# meter_mode.net
KiCad netlist of a schematic drawn in EAGLE
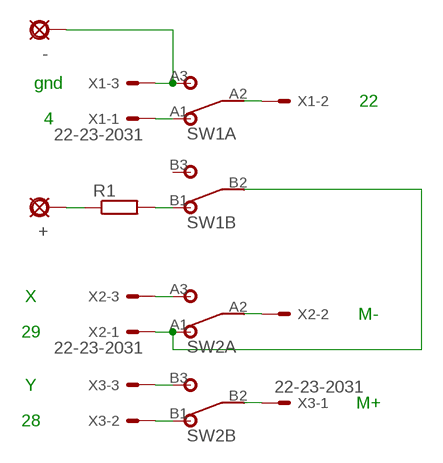
[diagram p0: schematic, sheet 1]

(export (version "E")
  (design (tool "Eeschema 10.0.6"))
  (components
    (comp (ref "+")
      (value "PADO")
      (footprint "eagle-import:ROUND")
      (libsource (lib "eagle-import") (part "PADO"))
    )
    (comp (ref "-")
      (value "PAD")
      (footprint "eagle-import:SQUARE")
      (libsource (lib "eagle-import") (part "PAD"))
    )
    (comp (ref "R1")
      (value "R-EU_0204/2V")
      (footprint "eagle-import:0204V")
      (libsource (lib "eagle-import") (part "R-EU_0204/2V"))
    )
    (comp (ref "SW1")
      (value "DPDT")
      (footprint "eagle-import:DPDT")
      (libsource (lib "eagle-import") (part "DPDT"))
    )
    (comp (ref "SW2")
      (value "DPDT")
      (footprint "eagle-import:DPDT")
      (libsource (lib "eagle-import") (part "DPDT"))
    )
    (comp (ref "X1")
      (value "22-23-2031")
      (footprint "eagle-import:22-23-2031")
      (fields (field (name "MF") "MOLEX"))
      (libsource (lib "eagle-import") (part "22-23-2031"))
    )
    (comp (ref "X2")
      (value "22-23-2031")
      (footprint "eagle-import:22-23-2031")
      (fields (field (name "MF") "MOLEX"))
      (libsource (lib "eagle-import") (part "22-23-2031"))
    )
    (comp (ref "X3")
      (value "22-23-2031")
      (footprint "eagle-import:22-23-2031")
      (fields (field (name "MF") "MOLEX"))
      (libsource (lib "eagle-import") (part "22-23-2031"))
    )
  )
  (nets
    (net (code "1") (name "Net-(+-PAD)") (class "Default")
      (node (ref "+") (pin "1") (pinfunction "PAD_1") (pintype "passive"))
      (node (ref "R1") (pin "1") (pinfunction "1_1") (pintype "passive"))
    )
    (net (code "2") (name "Net-(--PAD)") (class "Default")
      (node (ref "-") (pin "1") (pinfunction "PAD_1") (pintype "passive"))
      (node (ref "SW1") (pin "A3") (pinfunction "3_A3") (pintype "passive"))
      (node (ref "X1") (pin "3") (pinfunction "S_3") (pintype "passive"))
    )
    (net (code "3") (name "Net-(SW1A-1)") (class "Default")
      (node (ref "SW1") (pin "A1") (pinfunction "1_A1") (pintype "passive"))
      (node (ref "X1") (pin "1") (pinfunction "S_1") (pintype "passive"))
    )
    (net (code "4") (name "Net-(SW1A-2)") (class "Default")
      (node (ref "SW1") (pin "A2") (pinfunction "2_A2") (pintype "passive"))
      (node (ref "X1") (pin "2") (pinfunction "S_2") (pintype "passive"))
    )
    (net (code "5") (name "Net-(SW1B-1)") (class "Default")
      (node (ref "R1") (pin "2") (pinfunction "2_2") (pintype "passive"))
      (node (ref "SW1") (pin "B1") (pinfunction "1_B1") (pintype "passive"))
    )
    (net (code "6") (name "Net-(SW1B-2)") (class "Default")
      (node (ref "SW1") (pin "B2") (pinfunction "2_B2") (pintype "passive"))
      (node (ref "SW2") (pin "A1") (pinfunction "1_A1") (pintype "passive"))
      (node (ref "X2") (pin "1") (pinfunction "S_1") (pintype "passive"))
    )
    (net (code "7") (name "Net-(SW2A-2)") (class "Default")
      (node (ref "SW2") (pin "A2") (pinfunction "2_A2") (pintype "passive"))
      (node (ref "X2") (pin "2") (pinfunction "S_2") (pintype "passive"))
    )
    (net (code "8") (name "Net-(SW2A-3)") (class "Default")
      (node (ref "SW2") (pin "A3") (pinfunction "3_A3") (pintype "passive"))
      (node (ref "X2") (pin "3") (pinfunction "S_3") (pintype "passive"))
    )
    (net (code "9") (name "Net-(SW2B-1)") (class "Default")
      (node (ref "SW2") (pin "B1") (pinfunction "1_B1") (pintype "passive"))
      (node (ref "X3") (pin "2") (pinfunction "S_2") (pintype "passive"))
    )
    (net (code "10") (name "Net-(SW2B-2)") (class "Default")
      (node (ref "SW2") (pin "B2") (pinfunction "2_B2") (pintype "passive"))
      (node (ref "X3") (pin "1") (pinfunction "S_1") (pintype "passive"))
    )
    (net (code "11") (name "Net-(SW2B-3)") (class "Default")
      (node (ref "SW2") (pin "B3") (pinfunction "3_B3") (pintype "passive"))
      (node (ref "X3") (pin "3") (pinfunction "S_3") (pintype "passive"))
    )
    (net (code "12") (name "unconnected-(SW1B-3-PadB3)") (class "Default")
      (node (ref "SW1") (pin "B3") (pinfunction "3_B3") (pintype "passive"))
    )
  )
)
